# Sheet2.net
KiCad netlist of a schematic drawn in Altium Designer
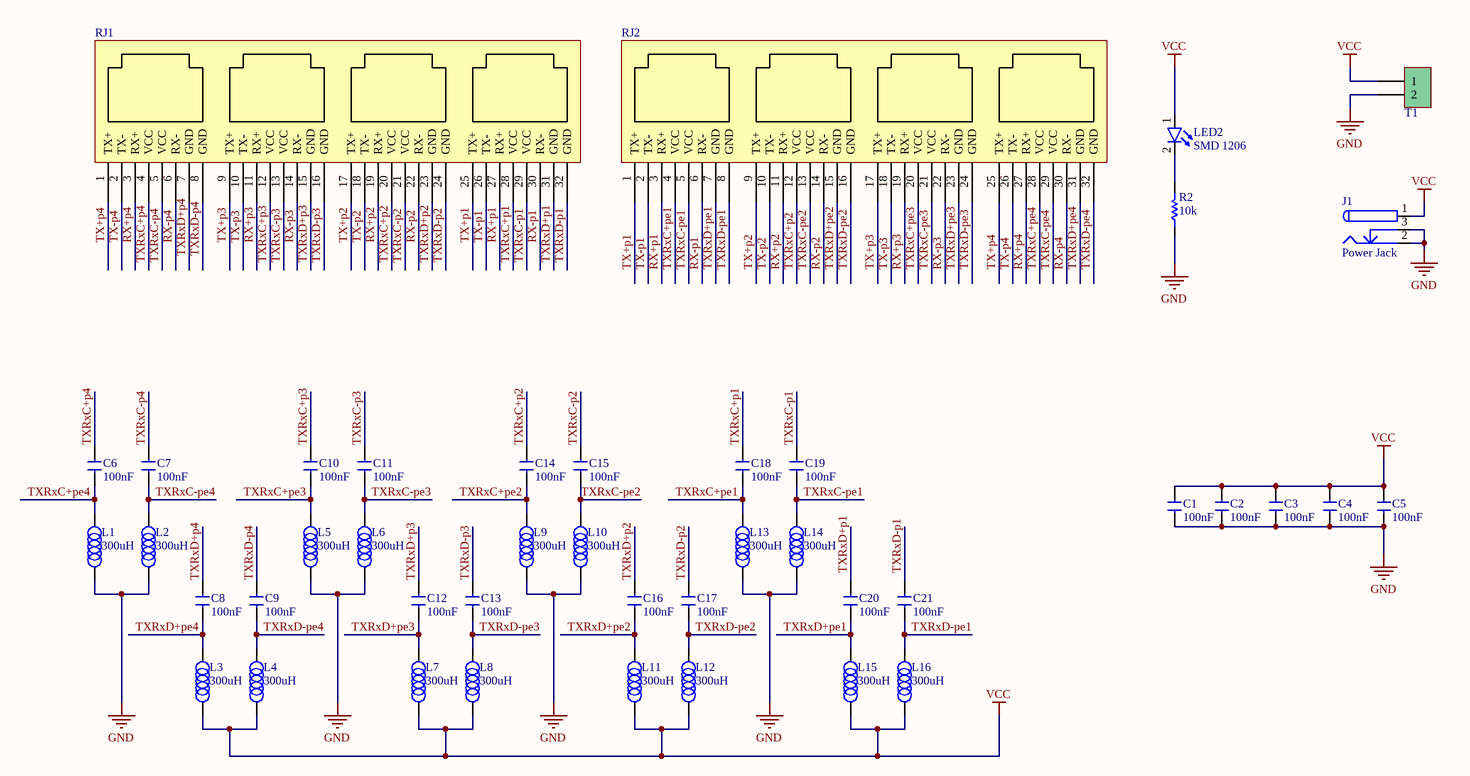
[diagram p0: Sheet2.SchDoc]

(export (version "E")
  (design (tool "Eeschema 10.0.6"))
  (components
    (comp (ref "C1")
      (value "Capacitor SMD")
      (footprint "1206 Capacitor")
      (fields (field (name "ALTIUM_UNNAMED_1") "100nF"))
      (libsource (lib "ZetaBoard_Lib") (part "Capacitor SMD"))
    )
    (comp (ref "C2")
      (value "Capacitor SMD")
      (footprint "1206 Capacitor")
      (fields (field (name "ALTIUM_UNNAMED_1") "100nF"))
      (libsource (lib "ZetaBoard_Lib") (part "Capacitor SMD"))
    )
    (comp (ref "C3")
      (value "Capacitor SMD")
      (footprint "1206 Capacitor")
      (fields (field (name "ALTIUM_UNNAMED_1") "100nF"))
      (libsource (lib "ZetaBoard_Lib") (part "Capacitor SMD"))
    )
    (comp (ref "C4")
      (value "Capacitor SMD")
      (footprint "1206 Capacitor")
      (fields (field (name "ALTIUM_UNNAMED_1") "100nF"))
      (libsource (lib "ZetaBoard_Lib") (part "Capacitor SMD"))
    )
    (comp (ref "C5")
      (value "Capacitor SMD")
      (footprint "1206 Capacitor")
      (fields (field (name "ALTIUM_UNNAMED_1") "100nF"))
      (libsource (lib "ZetaBoard_Lib") (part "Capacitor SMD"))
    )
    (comp (ref "C6")
      (value "Capacitor SMD")
      (footprint "1206 Capacitor")
      (fields (field (name "ALTIUM_UNNAMED_1") "100nF"))
      (libsource (lib "ZetaBoard_Lib") (part "Capacitor SMD"))
    )
    (comp (ref "C7")
      (value "Capacitor SMD")
      (footprint "1206 Capacitor")
      (fields (field (name "ALTIUM_UNNAMED_1") "100nF"))
      (libsource (lib "ZetaBoard_Lib") (part "Capacitor SMD"))
    )
    (comp (ref "C8")
      (value "Capacitor SMD")
      (footprint "1206 Capacitor")
      (fields (field (name "ALTIUM_UNNAMED_1") "100nF"))
      (libsource (lib "ZetaBoard_Lib") (part "Capacitor SMD"))
    )
    (comp (ref "C9")
      (value "Capacitor SMD")
      (footprint "1206 Capacitor")
      (fields (field (name "ALTIUM_UNNAMED_1") "100nF"))
      (libsource (lib "ZetaBoard_Lib") (part "Capacitor SMD"))
    )
    (comp (ref "C10")
      (value "Capacitor SMD")
      (footprint "1206 Capacitor")
      (fields (field (name "ALTIUM_UNNAMED_1") "100nF"))
      (libsource (lib "ZetaBoard_Lib") (part "Capacitor SMD"))
    )
    (comp (ref "C11")
      (value "Capacitor SMD")
      (footprint "1206 Capacitor")
      (fields (field (name "ALTIUM_UNNAMED_1") "100nF"))
      (libsource (lib "ZetaBoard_Lib") (part "Capacitor SMD"))
    )
    (comp (ref "C12")
      (value "Capacitor SMD")
      (footprint "1206 Capacitor")
      (fields (field (name "ALTIUM_UNNAMED_1") "100nF"))
      (libsource (lib "ZetaBoard_Lib") (part "Capacitor SMD"))
    )
    (comp (ref "C13")
      (value "Capacitor SMD")
      (footprint "1206 Capacitor")
      (fields (field (name "ALTIUM_UNNAMED_1") "100nF"))
      (libsource (lib "ZetaBoard_Lib") (part "Capacitor SMD"))
    )
    (comp (ref "C14")
      (value "Capacitor SMD")
      (footprint "1206 Capacitor")
      (fields (field (name "ALTIUM_UNNAMED_1") "100nF"))
      (libsource (lib "ZetaBoard_Lib") (part "Capacitor SMD"))
    )
    (comp (ref "C15")
      (value "Capacitor SMD")
      (footprint "1206 Capacitor")
      (fields (field (name "ALTIUM_UNNAMED_1") "100nF"))
      (libsource (lib "ZetaBoard_Lib") (part "Capacitor SMD"))
    )
    (comp (ref "C16")
      (value "Capacitor SMD")
      (footprint "1206 Capacitor")
      (fields (field (name "ALTIUM_UNNAMED_1") "100nF"))
      (libsource (lib "ZetaBoard_Lib") (part "Capacitor SMD"))
    )
    (comp (ref "C17")
      (value "Capacitor SMD")
      (footprint "1206 Capacitor")
      (fields (field (name "ALTIUM_UNNAMED_1") "100nF"))
      (libsource (lib "ZetaBoard_Lib") (part "Capacitor SMD"))
    )
    (comp (ref "C18")
      (value "Capacitor SMD")
      (footprint "1206 Capacitor")
      (fields (field (name "ALTIUM_UNNAMED_1") "100nF"))
      (libsource (lib "ZetaBoard_Lib") (part "Capacitor SMD"))
    )
    (comp (ref "C19")
      (value "Capacitor SMD")
      (footprint "1206 Capacitor")
      (fields (field (name "ALTIUM_UNNAMED_1") "100nF"))
      (libsource (lib "ZetaBoard_Lib") (part "Capacitor SMD"))
    )
    (comp (ref "C20")
      (value "Capacitor SMD")
      (footprint "1206 Capacitor")
      (fields (field (name "ALTIUM_UNNAMED_1") "100nF"))
      (libsource (lib "ZetaBoard_Lib") (part "Capacitor SMD"))
    )
    (comp (ref "C21")
      (value "Capacitor SMD")
      (footprint "1206 Capacitor")
      (fields (field (name "ALTIUM_UNNAMED_1") "100nF"))
      (libsource (lib "ZetaBoard_Lib") (part "Capacitor SMD"))
    )
    (comp (ref "J1")
      (value "Power Jack")
      (footprint "Power Jack")
      (fields (field (name "DESIGNER") "Saeid Jorablo"))
      (libsource (lib "Electrovolt Lib") (part "Power Jack"))
    )
    (comp (ref "L1")
      (value "300uH")
      (footprint "inductor")
      (libsource (lib "ZetaBoard_Lib") (part "Inductor SMT"))
    )
    (comp (ref "L2")
      (value "300uH")
      (footprint "inductor")
      (libsource (lib "ZetaBoard_Lib") (part "Inductor SMT"))
    )
    (comp (ref "L3")
      (value "300uH")
      (footprint "inductor")
      (libsource (lib "ZetaBoard_Lib") (part "Inductor SMT"))
    )
    (comp (ref "L4")
      (value "300uH")
      (footprint "inductor")
      (libsource (lib "ZetaBoard_Lib") (part "Inductor SMT"))
    )
    (comp (ref "L5")
      (value "300uH")
      (footprint "inductor")
      (libsource (lib "ZetaBoard_Lib") (part "Inductor SMT"))
    )
    (comp (ref "L6")
      (value "300uH")
      (footprint "inductor")
      (libsource (lib "ZetaBoard_Lib") (part "Inductor SMT"))
    )
    (comp (ref "L7")
      (value "300uH")
      (footprint "inductor")
      (libsource (lib "ZetaBoard_Lib") (part "Inductor SMT"))
    )
    (comp (ref "L8")
      (value "300uH")
      (footprint "inductor")
      (libsource (lib "ZetaBoard_Lib") (part "Inductor SMT"))
    )
    (comp (ref "L9")
      (value "300uH")
      (footprint "inductor")
      (libsource (lib "ZetaBoard_Lib") (part "Inductor SMT"))
    )
    (comp (ref "L10")
      (value "300uH")
      (footprint "inductor")
      (libsource (lib "ZetaBoard_Lib") (part "Inductor SMT"))
    )
    (comp (ref "L11")
      (value "300uH")
      (footprint "inductor")
      (libsource (lib "ZetaBoard_Lib") (part "Inductor SMT"))
    )
    (comp (ref "L12")
      (value "300uH")
      (footprint "inductor")
      (libsource (lib "ZetaBoard_Lib") (part "Inductor SMT"))
    )
    (comp (ref "L13")
      (value "300uH")
      (footprint "inductor")
      (libsource (lib "ZetaBoard_Lib") (part "Inductor SMT"))
    )
    (comp (ref "L14")
      (value "300uH")
      (footprint "inductor")
      (libsource (lib "ZetaBoard_Lib") (part "Inductor SMT"))
    )
    (comp (ref "L15")
      (value "300uH")
      (footprint "inductor")
      (libsource (lib "ZetaBoard_Lib") (part "Inductor SMT"))
    )
    (comp (ref "L16")
      (value "300uH")
      (footprint "inductor")
      (libsource (lib "ZetaBoard_Lib") (part "Inductor SMT"))
    )
    (comp (ref "LED2")
      (value "Red")
      (footprint "LED-5mm")
      (description "LED")
      (fields (field (name "SIZE") "SMD 1206") (field (name "DESIGNER") "Saeid Jorablo"))
      (libsource (lib "Electrovolt Lib") (part "LED"))
    )
    (comp (ref "R2")
      (value "10k")
      (footprint "RES 1206 (3216X08L)")
      (description "Resistor")
      (fields (field (name "TOLERANCE") "5%") (field (name "POWER") "1/8 W"))
      (libsource (lib "Electrovolt Lib") (part "Resistor"))
    )
    (comp (ref "RJ1") (value "~") (footprint "rj45-w57-4") (libsource (lib "Schlib1") (part "RJ45-w57-4")))
    (comp (ref "RJ2") (value "~") (footprint "rj45-w57-4") (libsource (lib "Schlib1") (part "RJ45-w57-4")))
    (comp (ref "T1")
      (value "Phoenix terminal")
      (footprint "phoenix terminal 2")
      (description "Terminal 2 Pin")
      (fields (field (name "DESIGNER") "Seyed Mohsen Ghasemain") (field (name "E-MAIL") "picpars@gmail.com"))
      (libsource (lib "usefully_Library") (part "Phoenix terminal 2"))
    )
  )
  (nets
    (net (code "1") (name "/RX+p1") (class "Default")
      (node (ref "RJ1") (pin "27") (pinfunction "RX+_27") (pintype "passive"))
      (node (ref "RJ2") (pin "3") (pinfunction "RX+_3") (pintype "passive"))
    )
    (net (code "2") (name "/RX+p2") (class "Default")
      (node (ref "RJ1") (pin "19") (pinfunction "RX+_19") (pintype "passive"))
      (node (ref "RJ2") (pin "11") (pinfunction "RX+_11") (pintype "passive"))
    )
    (net (code "3") (name "/RX+p3") (class "Default")
      (node (ref "RJ1") (pin "11") (pinfunction "RX+_11") (pintype "passive"))
      (node (ref "RJ2") (pin "19") (pinfunction "RX+_19") (pintype "passive"))
    )
    (net (code "4") (name "/RX+p4") (class "Default")
      (node (ref "RJ1") (pin "3") (pinfunction "RX+_3") (pintype "passive"))
      (node (ref "RJ2") (pin "27") (pinfunction "RX+_27") (pintype "passive"))
    )
    (net (code "5") (name "/RX-p1") (class "Default")
      (node (ref "RJ1") (pin "30") (pinfunction "RX-_30") (pintype "passive"))
      (node (ref "RJ2") (pin "6") (pinfunction "RX-_6") (pintype "passive"))
    )
    (net (code "6") (name "/RX-p2") (class "Default")
      (node (ref "RJ1") (pin "22") (pinfunction "RX-_22") (pintype "passive"))
      (node (ref "RJ2") (pin "14") (pinfunction "RX-_14") (pintype "passive"))
    )
    (net (code "7") (name "/RX-p3") (class "Default")
      (node (ref "RJ1") (pin "14") (pinfunction "RX-_14") (pintype "passive"))
      (node (ref "RJ2") (pin "22") (pinfunction "RX-_22") (pintype "passive"))
    )
    (net (code "8") (name "/RX-p4") (class "Default")
      (node (ref "RJ1") (pin "6") (pinfunction "RX-_6") (pintype "passive"))
      (node (ref "RJ2") (pin "30") (pinfunction "RX-_30") (pintype "passive"))
    )
    (net (code "9") (name "/TX+p1") (class "Default")
      (node (ref "RJ1") (pin "25") (pinfunction "TX+_25") (pintype "passive"))
      (node (ref "RJ2") (pin "1") (pinfunction "TX+_1") (pintype "passive"))
    )
    (net (code "10") (name "/TX+p2") (class "Default")
      (node (ref "RJ1") (pin "17") (pinfunction "TX+_17") (pintype "passive"))
      (node (ref "RJ2") (pin "9") (pinfunction "TX+_9") (pintype "passive"))
    )
    (net (code "11") (name "/TX+p3") (class "Default")
      (node (ref "RJ1") (pin "9") (pinfunction "TX+_9") (pintype "passive"))
      (node (ref "RJ2") (pin "17") (pinfunction "TX+_17") (pintype "passive"))
    )
    (net (code "12") (name "/TX+p4") (class "Default")
      (node (ref "RJ1") (pin "1") (pinfunction "TX+_1") (pintype "passive"))
      (node (ref "RJ2") (pin "25") (pinfunction "TX+_25") (pintype "passive"))
    )
    (net (code "13") (name "/TX-p1") (class "Default")
      (node (ref "RJ1") (pin "26") (pinfunction "TX-_26") (pintype "passive"))
      (node (ref "RJ2") (pin "2") (pinfunction "TX-_2") (pintype "passive"))
    )
    (net (code "14") (name "/TX-p2") (class "Default")
      (node (ref "RJ1") (pin "18") (pinfunction "TX-_18") (pintype "passive"))
      (node (ref "RJ2") (pin "10") (pinfunction "TX-_10") (pintype "passive"))
    )
    (net (code "15") (name "/TX-p3") (class "Default")
      (node (ref "RJ1") (pin "10") (pinfunction "TX-_10") (pintype "passive"))
      (node (ref "RJ2") (pin "18") (pinfunction "TX-_18") (pintype "passive"))
    )
    (net (code "16") (name "/TX-p4") (class "Default")
      (node (ref "RJ1") (pin "2") (pinfunction "TX-_2") (pintype "passive"))
      (node (ref "RJ2") (pin "26") (pinfunction "TX-_26") (pintype "passive"))
    )
    (net (code "17") (name "/TXRxC+p1") (class "Default")
      (node (ref "C18") (pin "2") (pintype "passive"))
      (node (ref "RJ1") (pin "28") (pinfunction "VCC_28") (pintype "passive"))
    )
    (net (code "18") (name "/TXRxC+p2") (class "Default")
      (node (ref "C14") (pin "2") (pintype "passive"))
      (node (ref "RJ1") (pin "20") (pinfunction "VCC_20") (pintype "passive"))
      (node (ref "RJ2") (pin "12") (pinfunction "VCC_12") (pintype "passive"))
    )
    (net (code "19") (name "/TXRxC+p3") (class "Default")
      (node (ref "C10") (pin "2") (pintype "passive"))
      (node (ref "RJ1") (pin "12") (pinfunction "VCC_12") (pintype "passive"))
    )
    (net (code "20") (name "/TXRxC+p4") (class "Default")
      (node (ref "C6") (pin "2") (pintype "passive"))
      (node (ref "RJ1") (pin "4") (pinfunction "VCC_4") (pintype "passive"))
    )
    (net (code "21") (name "/TXRxC+pe1") (class "Default")
      (node (ref "C18") (pin "1") (pintype "passive"))
      (node (ref "L13") (pin "2") (pintype "passive"))
      (node (ref "RJ2") (pin "4") (pinfunction "VCC_4") (pintype "passive"))
    )
    (net (code "22") (name "/TXRxC+pe2") (class "Default")
      (node (ref "C14") (pin "1") (pintype "passive"))
      (node (ref "L9") (pin "2") (pintype "passive"))
    )
    (net (code "23") (name "/TXRxC+pe3") (class "Default")
      (node (ref "C10") (pin "1") (pintype "passive"))
      (node (ref "L5") (pin "2") (pintype "passive"))
      (node (ref "RJ2") (pin "20") (pinfunction "VCC_20") (pintype "passive"))
    )
    (net (code "24") (name "/TXRxC+pe4") (class "Default")
      (node (ref "C6") (pin "1") (pintype "passive"))
      (node (ref "L1") (pin "2") (pintype "passive"))
      (node (ref "RJ2") (pin "28") (pinfunction "VCC_28") (pintype "passive"))
    )
    (net (code "25") (name "/TXRxC-p1") (class "Default")
      (node (ref "C19") (pin "2") (pintype "passive"))
      (node (ref "RJ1") (pin "29") (pinfunction "VCC_29") (pintype "passive"))
    )
    (net (code "26") (name "/TXRxC-p2") (class "Default")
      (node (ref "C15") (pin "2") (pintype "passive"))
      (node (ref "RJ1") (pin "21") (pinfunction "VCC_21") (pintype "passive"))
    )
    (net (code "27") (name "/TXRxC-p3") (class "Default")
      (node (ref "C11") (pin "2") (pintype "passive"))
      (node (ref "RJ1") (pin "13") (pinfunction "VCC_13") (pintype "passive"))
    )
    (net (code "28") (name "/TXRxC-p4") (class "Default")
      (node (ref "C7") (pin "2") (pintype "passive"))
      (node (ref "RJ1") (pin "5") (pinfunction "VCC_5") (pintype "passive"))
    )
    (net (code "29") (name "/TXRxC-pe1") (class "Default")
      (node (ref "C19") (pin "1") (pintype "passive"))
      (node (ref "L14") (pin "2") (pintype "passive"))
      (node (ref "RJ2") (pin "5") (pinfunction "VCC_5") (pintype "passive"))
    )
    (net (code "30") (name "/TXRxC-pe2") (class "Default")
      (node (ref "C15") (pin "1") (pintype "passive"))
      (node (ref "L10") (pin "2") (pintype "passive"))
      (node (ref "RJ2") (pin "13") (pinfunction "VCC_13") (pintype "passive"))
    )
    (net (code "31") (name "/TXRxC-pe3") (class "Default")
      (node (ref "C11") (pin "1") (pintype "passive"))
      (node (ref "L6") (pin "2") (pintype "passive"))
      (node (ref "RJ2") (pin "21") (pinfunction "VCC_21") (pintype "passive"))
    )
    (net (code "32") (name "/TXRxC-pe4") (class "Default")
      (node (ref "C7") (pin "1") (pintype "passive"))
      (node (ref "L2") (pin "2") (pintype "passive"))
      (node (ref "RJ2") (pin "29") (pinfunction "VCC_29") (pintype "passive"))
    )
    (net (code "33") (name "/TXRxD+p1") (class "Default")
      (node (ref "C20") (pin "2") (pintype "passive"))
      (node (ref "RJ1") (pin "31") (pinfunction "GND_31") (pintype "passive"))
    )
    (net (code "34") (name "/TXRxD+p2") (class "Default")
      (node (ref "C16") (pin "2") (pintype "passive"))
      (node (ref "RJ1") (pin "23") (pinfunction "GND_23") (pintype "passive"))
    )
    (net (code "35") (name "/TXRxD+p3") (class "Default")
      (node (ref "C12") (pin "2") (pintype "passive"))
      (node (ref "RJ1") (pin "15") (pinfunction "GND_15") (pintype "passive"))
    )
    (net (code "36") (name "/TXRxD+p4") (class "Default")
      (node (ref "C8") (pin "2") (pintype "passive"))
      (node (ref "RJ1") (pin "7") (pinfunction "GND_7") (pintype "passive"))
    )
    (net (code "37") (name "/TXRxD+pe1") (class "Default")
      (node (ref "C20") (pin "1") (pintype "passive"))
      (node (ref "L15") (pin "2") (pintype "passive"))
      (node (ref "RJ2") (pin "7") (pinfunction "GND_7") (pintype "passive"))
    )
    (net (code "38") (name "/TXRxD+pe2") (class "Default")
      (node (ref "C16") (pin "1") (pintype "passive"))
      (node (ref "L11") (pin "2") (pintype "passive"))
      (node (ref "RJ2") (pin "15") (pinfunction "GND_15") (pintype "passive"))
    )
    (net (code "39") (name "/TXRxD+pe3") (class "Default")
      (node (ref "C12") (pin "1") (pintype "passive"))
      (node (ref "L7") (pin "2") (pintype "passive"))
      (node (ref "RJ2") (pin "23") (pinfunction "GND_23") (pintype "passive"))
    )
    (net (code "40") (name "/TXRxD+pe4") (class "Default")
      (node (ref "C8") (pin "1") (pintype "passive"))
      (node (ref "L3") (pin "2") (pintype "passive"))
      (node (ref "RJ2") (pin "31") (pinfunction "GND_31") (pintype "passive"))
    )
    (net (code "41") (name "/TXRxD-p1") (class "Default")
      (node (ref "C21") (pin "2") (pintype "passive"))
      (node (ref "RJ1") (pin "32") (pinfunction "GND_32") (pintype "passive"))
    )
    (net (code "42") (name "/TXRxD-p2") (class "Default")
      (node (ref "C17") (pin "2") (pintype "passive"))
      (node (ref "RJ1") (pin "24") (pinfunction "GND_24") (pintype "passive"))
    )
    (net (code "43") (name "/TXRxD-p3") (class "Default")
      (node (ref "C13") (pin "2") (pintype "passive"))
      (node (ref "RJ1") (pin "16") (pinfunction "GND_16") (pintype "passive"))
    )
    (net (code "44") (name "/TXRxD-p4") (class "Default")
      (node (ref "C9") (pin "2") (pintype "passive"))
      (node (ref "RJ1") (pin "8") (pinfunction "GND_8") (pintype "passive"))
    )
    (net (code "45") (name "/TXRxD-pe1") (class "Default")
      (node (ref "C21") (pin "1") (pintype "passive"))
      (node (ref "L16") (pin "2") (pintype "passive"))
      (node (ref "RJ2") (pin "8") (pinfunction "GND_8") (pintype "passive"))
    )
    (net (code "46") (name "/TXRxD-pe2") (class "Default")
      (node (ref "C17") (pin "1") (pintype "passive"))
      (node (ref "L12") (pin "2") (pintype "passive"))
      (node (ref "RJ2") (pin "16") (pinfunction "GND_16") (pintype "passive"))
    )
    (net (code "47") (name "/TXRxD-pe3") (class "Default")
      (node (ref "C13") (pin "1") (pintype "passive"))
      (node (ref "L8") (pin "2") (pintype "passive"))
      (node (ref "RJ2") (pin "24") (pinfunction "GND_24") (pintype "passive"))
    )
    (net (code "48") (name "/TXRxD-pe4") (class "Default")
      (node (ref "C9") (pin "1") (pintype "passive"))
      (node (ref "L4") (pin "2") (pintype "passive"))
      (node (ref "RJ2") (pin "32") (pinfunction "GND_32") (pintype "passive"))
    )
    (net (code "49") (name "GND") (class "Default")
      (node (ref "C1") (pin "1") (pintype "passive"))
      (node (ref "C2") (pin "1") (pintype "passive"))
      (node (ref "C3") (pin "1") (pintype "passive"))
      (node (ref "C4") (pin "1") (pintype "passive"))
      (node (ref "C5") (pin "1") (pintype "passive"))
      (node (ref "J1") (pin "2") (pinfunction "2_2") (pintype "power_in"))
      (node (ref "J1") (pin "3") (pinfunction "3_3") (pintype "power_in"))
      (node (ref "L1") (pin "1") (pintype "passive"))
      (node (ref "L10") (pin "1") (pintype "passive"))
      (node (ref "L13") (pin "1") (pintype "passive"))
      (node (ref "L14") (pin "1") (pintype "passive"))
      (node (ref "L2") (pin "1") (pintype "passive"))
      (node (ref "L5") (pin "1") (pintype "passive"))
      (node (ref "L6") (pin "1") (pintype "passive"))
      (node (ref "L9") (pin "1") (pintype "passive"))
      (node (ref "R2") (pin "1") (pinfunction "1_1") (pintype "passive"))
      (node (ref "T1") (pin "2") (pinfunction "2_2") (pintype "passive"))
    )
    (net (code "50") (name "Net-(LED2-K)") (class "Default")
      (node (ref "LED2") (pin "2") (pinfunction "K_2") (pintype "passive"))
      (node (ref "R2") (pin "2") (pinfunction "2_2") (pintype "passive"))
    )
    (net (code "51") (name "VCC") (class "Default")
      (node (ref "C1") (pin "2") (pintype "passive"))
      (node (ref "C2") (pin "2") (pintype "passive"))
      (node (ref "C3") (pin "2") (pintype "passive"))
      (node (ref "C4") (pin "2") (pintype "passive"))
      (node (ref "C5") (pin "2") (pintype "passive"))
      (node (ref "J1") (pin "1") (pinfunction "1_1") (pintype "power_in"))
      (node (ref "L11") (pin "1") (pintype "passive"))
      (node (ref "L12") (pin "1") (pintype "passive"))
      (node (ref "L15") (pin "1") (pintype "passive"))
      (node (ref "L16") (pin "1") (pintype "passive"))
      (node (ref "L3") (pin "1") (pintype "passive"))
      (node (ref "L4") (pin "1") (pintype "passive"))
      (node (ref "L7") (pin "1") (pintype "passive"))
      (node (ref "L8") (pin "1") (pintype "passive"))
      (node (ref "LED2") (pin "1") (pinfunction "A_1") (pintype "passive"))
      (node (ref "T1") (pin "1") (pinfunction "1_1") (pintype "passive"))
    )
  )
)
